# Boost.net
KiCad netlist of a schematic drawn in Altium Designer
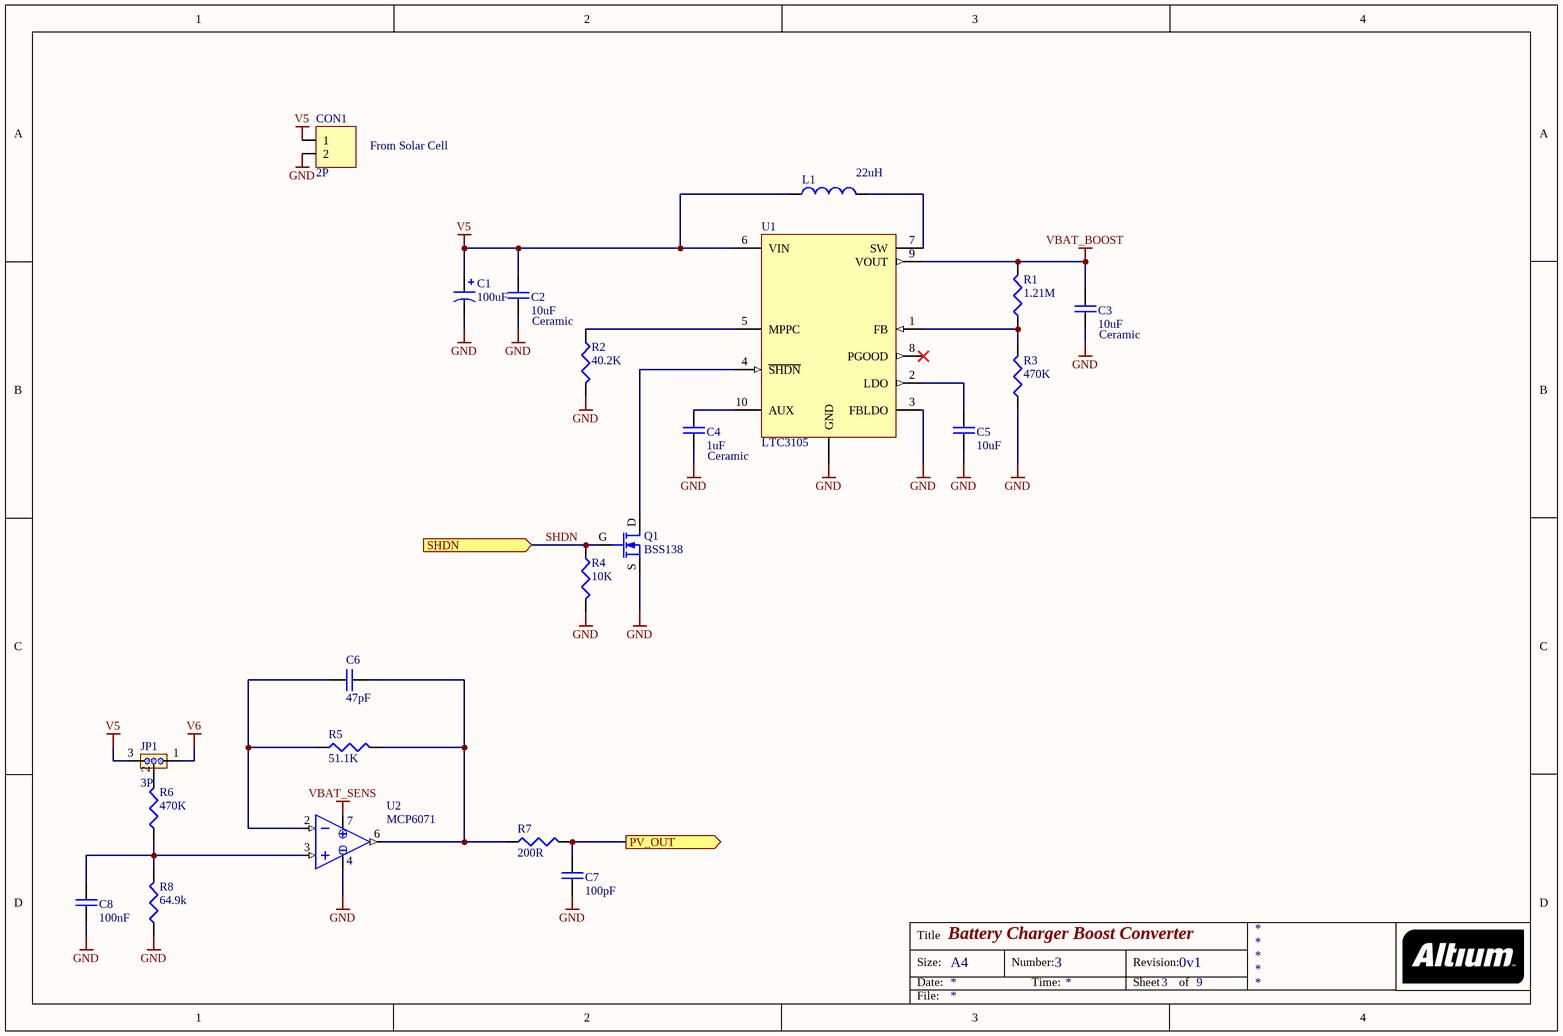
[diagram p0: Boost.SchDoc]

(export (version "E")
  (design (tool "Eeschema 10.0.6"))
  (components
    (comp (ref "C1")
      (value "100uF")
      (footprint "RADIAL-5MM")
      (description "Polarized Capacitor")
      (fields (field (name "OWNER") "Nuno Brum"))
      (libsource (lib "Alcetronics_Devices") (part "CAP POL"))
    )
    (comp (ref "C2")
      (value "10uF")
      (footprint "0805")
      (description "Capacitor")
      (fields (field (name "OWNER") "Nuno Brum"))
      (libsource (lib "Alcetronics_Devices") (part "CAP"))
    )
    (comp (ref "C3")
      (value "10uF")
      (footprint "0805")
      (description "Capacitor")
      (fields (field (name "OWNER") "Nuno Brum"))
      (libsource (lib "Alcetronics_Devices") (part "CAP"))
    )
    (comp (ref "C4")
      (value "1uF")
      (footprint "0603")
      (description "Capacitor")
      (fields (field (name "OWNER") "Nuno Brum"))
      (libsource (lib "Alcetronics_Devices") (part "CAP"))
    )
    (comp (ref "C5")
      (value "10uF")
      (footprint "0805")
      (description "Capacitor")
      (fields (field (name "OWNER") "Nuno Brum"))
      (libsource (lib "Alcetronics_Devices") (part "CAP"))
    )
    (comp (ref "C6")
      (value "47pF")
      (footprint "0603")
      (description "Capacitor")
      (fields (field (name "OWNER") "Nuno Brum"))
      (libsource (lib "Alcetronics_Devices") (part "CAP"))
    )
    (comp (ref "C7")
      (value "100pF")
      (footprint "0603")
      (description "Capacitor")
      (fields (field (name "OWNER") "Nuno Brum"))
      (libsource (lib "Alcetronics_Devices") (part "CAP"))
    )
    (comp (ref "C8")
      (value "100nF")
      (footprint "0603")
      (description "Capacitor")
      (fields (field (name "OWNER") "Nuno Brum"))
      (libsource (lib "Alcetronics_Devices") (part "CAP"))
    )
    (comp (ref "CON1")
      (value "2P")
      (footprint "JST-2MM")
      (description "Connector 2 pins")
      (fields (field (name "OWNER") "Rui Rebelo"))
      (libsource (lib "Alcetronics_EM") (part "CON02"))
    )
    (comp (ref "JP1")
      (value "3P")
      (footprint "SIP-3")
      (description "3-Jumper")
      (fields (field (name "OWNER") "Nuno Brum"))
      (libsource (lib "Alcetronics_EM") (part "JMP3"))
    )
    (comp (ref "L1")
      (value "22uH")
      (footprint "7X7")
      (description "Inductor")
      (fields (field (name "OWNER") "Nuno Brum"))
      (libsource (lib "Alcetronics_Devices") (part "IND"))
    )
    (comp (ref "Q1")
      (value "BSS138")
      (footprint "SOT-23@GSD")
      (description "N-Channel Logic Level Enhancement Mode Field Effect Transistor")
      (fields (field (name "OWNER") "Nuno Brum"))
      (libsource (lib "Alcetronics_Devices") (part "MOSFET-N"))
    )
    (comp (ref "R1")
      (value "1.21M")
      (footprint "0603")
      (description "Resistor")
      (fields (field (name "OWNER") "Nuno Brum"))
      (libsource (lib "Alcetronics_Devices") (part "RES"))
    )
    (comp (ref "R2")
      (value "40.2K")
      (footprint "0603")
      (description "Resistor")
      (fields (field (name "OWNER") "Nuno Brum"))
      (libsource (lib "Alcetronics_Devices") (part "RES"))
    )
    (comp (ref "R3")
      (value "470K")
      (footprint "0603")
      (description "Resistor")
      (fields (field (name "OWNER") "Nuno Brum"))
      (libsource (lib "Alcetronics_Devices") (part "RES"))
    )
    (comp (ref "R4")
      (value "10K")
      (footprint "0603")
      (description "Resistor")
      (fields (field (name "OWNER") "Nuno Brum"))
      (libsource (lib "Alcetronics_Devices") (part "RES"))
    )
    (comp (ref "R5")
      (value "51.1K")
      (footprint "0603")
      (description "Resistor")
      (fields (field (name "OWNER") "Nuno Brum"))
      (libsource (lib "Alcetronics_Devices") (part "RES"))
    )
    (comp (ref "R6")
      (value "470K")
      (footprint "0603")
      (description "Resistor")
      (fields (field (name "OWNER") "Nuno Brum"))
      (libsource (lib "Alcetronics_Devices") (part "RES"))
    )
    (comp (ref "R7")
      (value "200R")
      (footprint "0603")
      (description "Resistor")
      (fields (field (name "OWNER") "Nuno Brum"))
      (libsource (lib "Alcetronics_Devices") (part "RES"))
    )
    (comp (ref "R8")
      (value "64.9k")
      (footprint "0603")
      (description "Resistor")
      (fields (field (name "OWNER") "Nuno Brum"))
      (libsource (lib "Alcetronics_Devices") (part "RES"))
    )
    (comp (ref "U1")
      (value "LTC3105")
      (footprint "DFN-10")
      (description "400mA Step-Up DCDC Converter With MPPC and 250mV Start-Up")
      (libsource (lib "Alcetronics_IC") (part "LTC3105"))
    )
    (comp (ref "U2")
      (value "MCP6071")
      (footprint "SOIC-8")
      (description "Low-Offset Opamp")
      (libsource (lib "Alcetronics_IC") (part "MCP6V26"))
    )
  )
  (nets
    (net (code "1") (name "/PV_OUT") (class "Default")
      (node (ref "C7") (pin "2") (pinfunction "2_2") (pintype "passive"))
      (node (ref "R7") (pin "2") (pinfunction "2_2") (pintype "passive"))
    )
    (net (code "2") (name "/SHDN") (class "Default")
      (node (ref "Q1") (pin "G") (pinfunction "G_G") (pintype "passive"))
      (node (ref "R4") (pin "1") (pinfunction "1_1") (pintype "passive"))
    )
    (net (code "3") (name "GND") (class "Default")
      (node (ref "C1") (pin "2") (pinfunction "N_2") (pintype "passive"))
      (node (ref "C2") (pin "1") (pinfunction "1_1") (pintype "passive"))
      (node (ref "C3") (pin "1") (pinfunction "1_1") (pintype "passive"))
      (node (ref "C4") (pin "1") (pinfunction "1_1") (pintype "passive"))
      (node (ref "C5") (pin "1") (pinfunction "1_1") (pintype "passive"))
      (node (ref "C7") (pin "1") (pinfunction "1_1") (pintype "passive"))
      (node (ref "C8") (pin "1") (pinfunction "1_1") (pintype "passive"))
      (node (ref "CON1") (pin "2") (pinfunction "2_2") (pintype "passive"))
      (node (ref "Q1") (pin "S") (pinfunction "S_S") (pintype "passive"))
      (node (ref "R2") (pin "2") (pinfunction "2_2") (pintype "passive"))
      (node (ref "R3") (pin "1") (pinfunction "1_1") (pintype "passive"))
      (node (ref "R4") (pin "2") (pinfunction "2_2") (pintype "passive"))
      (node (ref "R8") (pin "1") (pinfunction "1_1") (pintype "passive"))
      (node (ref "U1") (pin "3") (pinfunction "FBLDO_3") (pintype "passive"))
      (node (ref "U1") (pin "PAD") (pinfunction "GND_PAD") (pintype "passive"))
      (node (ref "U2") (pin "4") (pinfunction "VSS_4") (pintype "power_in"))
    )
    (net (code "4") (name "Net-(JP1-Pad2)") (class "Default")
      (node (ref "JP1") (pin "2") (pinfunction "2_2") (pintype "passive"))
      (node (ref "R6") (pin "2") (pinfunction "2_2") (pintype "passive"))
    )
    (net (code "5") (name "Net-(U1-AUX)") (class "Default")
      (node (ref "C4") (pin "2") (pinfunction "2_2") (pintype "passive"))
      (node (ref "U1") (pin "10") (pinfunction "AUX_10") (pintype "passive"))
    )
    (net (code "6") (name "Net-(U1-FB)") (class "Default")
      (node (ref "R1") (pin "1") (pinfunction "1_1") (pintype "passive"))
      (node (ref "R3") (pin "2") (pinfunction "2_2") (pintype "passive"))
      (node (ref "U1") (pin "1") (pinfunction "FB_1") (pintype "input"))
    )
    (net (code "7") (name "Net-(U1-LDO)") (class "Default")
      (node (ref "C5") (pin "2") (pinfunction "2_2") (pintype "passive"))
      (node (ref "U1") (pin "2") (pinfunction "LDO_2") (pintype "output"))
    )
    (net (code "8") (name "Net-(U1-MPPC)") (class "Default")
      (node (ref "R2") (pin "1") (pinfunction "1_1") (pintype "passive"))
      (node (ref "U1") (pin "5") (pinfunction "MPPC_5") (pintype "passive"))
    )
    (net (code "9") (name "Net-(U1-SW)") (class "Default")
      (node (ref "L1") (pin "2") (pinfunction "2_2") (pintype "passive"))
      (node (ref "U1") (pin "7") (pinfunction "SW_7") (pintype "power_in"))
    )
    (net (code "10") (name "Net-(U1-~{SHDN})") (class "Default")
      (node (ref "Q1") (pin "D") (pinfunction "D_D") (pintype "passive"))
      (node (ref "U1") (pin "4") (pinfunction "~{SHDN}_4") (pintype "input"))
    )
    (net (code "11") (name "Net-(U2-INN)") (class "Default")
      (node (ref "C6") (pin "1") (pinfunction "1_1") (pintype "passive"))
      (node (ref "R5") (pin "1") (pinfunction "1_1") (pintype "passive"))
      (node (ref "U2") (pin "2") (pinfunction "INN_2") (pintype "input"))
    )
    (net (code "12") (name "Net-(U2-INP)") (class "Default")
      (node (ref "C8") (pin "2") (pinfunction "2_2") (pintype "passive"))
      (node (ref "R6") (pin "1") (pinfunction "1_1") (pintype "passive"))
      (node (ref "R8") (pin "2") (pinfunction "2_2") (pintype "passive"))
      (node (ref "U2") (pin "3") (pinfunction "INP_3") (pintype "input"))
    )
    (net (code "13") (name "Net-(U2-VOUT)") (class "Default")
      (node (ref "C6") (pin "2") (pinfunction "2_2") (pintype "passive"))
      (node (ref "R5") (pin "2") (pinfunction "2_2") (pintype "passive"))
      (node (ref "R7") (pin "1") (pinfunction "1_1") (pintype "passive"))
      (node (ref "U2") (pin "6") (pinfunction "VOUT_6") (pintype "output"))
    )
    (net (code "14") (name "V5") (class "Default")
      (node (ref "C1") (pin "1") (pinfunction "P_1") (pintype "passive"))
      (node (ref "C2") (pin "2") (pinfunction "2_2") (pintype "passive"))
      (node (ref "CON1") (pin "1") (pinfunction "1_1") (pintype "passive"))
      (node (ref "JP1") (pin "3") (pinfunction "3_3") (pintype "passive"))
      (node (ref "L1") (pin "1") (pinfunction "1_1") (pintype "passive"))
      (node (ref "U1") (pin "6") (pinfunction "VIN_6") (pintype "passive"))
    )
    (net (code "15") (name "V6") (class "Default")
      (node (ref "JP1") (pin "1") (pinfunction "1_1") (pintype "passive"))
    )
    (net (code "16") (name "VBAT_BOOST") (class "Default")
      (node (ref "C3") (pin "2") (pinfunction "2_2") (pintype "passive"))
      (node (ref "R1") (pin "2") (pinfunction "2_2") (pintype "passive"))
      (node (ref "U1") (pin "9") (pinfunction "VOUT_9") (pintype "output"))
    )
    (net (code "17") (name "VBAT_SENS") (class "Default")
      (node (ref "U2") (pin "7") (pinfunction "VDD_7") (pintype "power_in"))
    )
    (net (code "18") (name "unconnected-(U1-PGOOD-Pad8)") (class "Default")
      (node (ref "U1") (pin "8") (pinfunction "PGOOD_8") (pintype "output+no_connect"))
    )
  )
)
